# SD_Card.net
KiCad netlist of a schematic drawn in Altium Designer
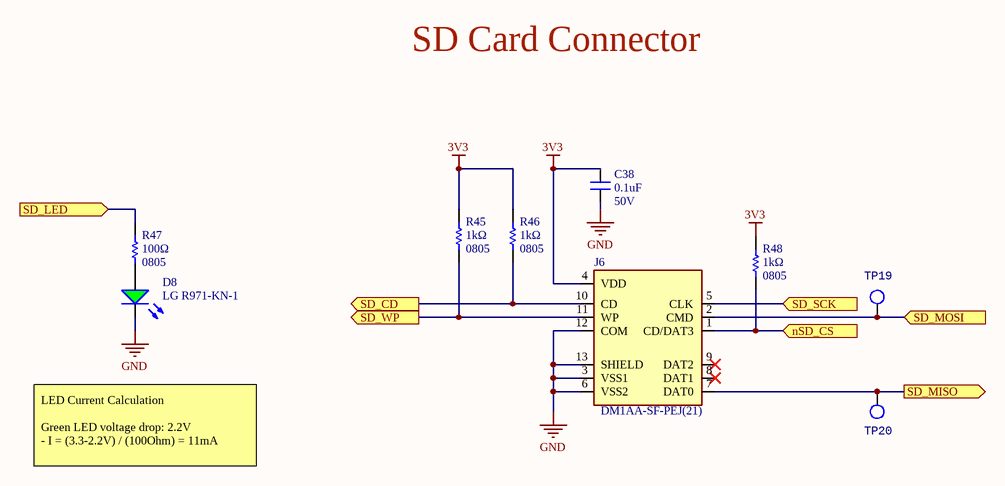
[diagram p0: SD Card.SchDoc]

(export (version "E")
  (design (tool "Eeschema 10.0.6"))
  (components
    (comp (ref "C38")
      (value "0.1uF")
      (footprint "CAPC2012X140N")
      (description "CAP CER 0.1UF 50V X7R 0805")
      (fields
        (field (name "TOLERANCE") "10%")
        (field (name "VOLTAGE RATING") "50V")
        (field (name "Comment") "CAP_0.1uF_50V_0805")
      )
      (libsource (lib "UWRT_Schematic_Library_2020") (part "CAP_0.1uF_50V_0805"))
    )
    (comp (ref "D8")
      (value "DIO_LED_G")
      (footprint "LED_0805_LINE")
      (description "LED GREEN DIFFUSED 0805 SMD")
      (fields (field (name "MANUFACTURER PART NUMBER 1") "LG R971-KN-1"))
      (libsource (lib "UWRT_Schematic_Library_2020") (part "DIO_LED_G"))
    )
    (comp (ref "J6")
      (value "SD_CARD_CON")
      (footprint "HRS_DM1AA-SF-PEJ(21)")
      (description "12 _9 + 3_ Position Card Connector Secure Digital - SD Surface Mount, Right Angle Gold")
      (fields (field (name "MANUFACTURER PART NUMBER 1") "DM1AA-SF-PEJ(21)"))
      (libsource (lib "UWRT_Schematic_Library_2020") (part "SD_CARD_CON"))
    )
    (comp (ref "R45")
      (value "1kΩ")
      (footprint "RESC2012X60N")
      (description "RES SMD 1K OHM 1% 1/8W 0805")
      (fields
        (field (name "CASE CODE (IMPERIAL)") "0805")
        (field (name "TOLERANCE") "1%")
        (field (name "Comment") "RES_1kΩ_0805")
      )
      (libsource (lib "UWRT_Schematic_Library_2020") (part "RES_1kΩ_0805"))
    )
    (comp (ref "R46")
      (value "1kΩ")
      (footprint "RESC2012X60N")
      (description "RES SMD 1K OHM 1% 1/8W 0805")
      (fields
        (field (name "CASE CODE (IMPERIAL)") "0805")
        (field (name "TOLERANCE") "1%")
        (field (name "Comment") "RES_1kΩ_0805")
      )
      (libsource (lib "UWRT_Schematic_Library_2020") (part "RES_1kΩ_0805"))
    )
    (comp (ref "R47")
      (value "100Ω")
      (footprint "RESC2012X60N")
      (description "RES SMD 100 OHM 1% 1/8W 0805")
      (fields (field (name "CASE CODE (IMPERIAL)") "0805") (field (name "Comment") "RES_100Ω_0805"))
      (libsource (lib "UWRT_Schematic_Library_2020") (part "RES_100Ω_0805"))
    )
    (comp (ref "R48")
      (value "1kΩ")
      (footprint "RESC2012X60N")
      (description "RES SMD 1K OHM 1% 1/8W 0805")
      (fields
        (field (name "CASE CODE (IMPERIAL)") "0805")
        (field (name "TOLERANCE") "1%")
        (field (name "Comment") "RES_1kΩ_0805")
      )
      (libsource (lib "UWRT_Schematic_Library_2020") (part "RES_1kΩ_0805"))
    )
    (comp (ref "TP19")
      (value "TESTPOINT_LOOP")
      (footprint "TESTPOINT_LOOP")
      (description "Loop testpoint through-hole pad")
      (libsource (lib "UWRT_Schematic_Library_2020") (part "TESTPOINT_LOOP"))
    )
    (comp (ref "TP20")
      (value "TESTPOINT_LOOP")
      (footprint "TESTPOINT_LOOP")
      (description "Loop testpoint through-hole pad")
      (libsource (lib "UWRT_Schematic_Library_2020") (part "TESTPOINT_LOOP"))
    )
  )
  (nets
    (net (code "1") (name "/SD_CD") (class "Default")
      (node (ref "J6") (pin "10") (pinfunction "CD_10") (pintype "passive"))
      (node (ref "R46") (pin "1") (pinfunction "1_1") (pintype "passive"))
    )
    (net (code "2") (name "/SD_LED") (class "Default")
      (node (ref "R47") (pin "2") (pinfunction "2_2") (pintype "passive"))
    )
    (net (code "3") (name "/SD_MISO") (class "Default")
      (node (ref "J6") (pin "7") (pinfunction "DAT0_7") (pintype "passive"))
      (node (ref "TP20") (pin "1") (pintype "passive"))
    )
    (net (code "4") (name "/SD_MOSI") (class "Default")
      (node (ref "J6") (pin "2") (pinfunction "CMD_2") (pintype "passive"))
      (node (ref "TP19") (pin "1") (pintype "passive"))
    )
    (net (code "5") (name "/SD_SCK") (class "Default")
      (node (ref "J6") (pin "5") (pinfunction "CLK_5") (pintype "passive"))
    )
    (net (code "6") (name "/SD_WP") (class "Default")
      (node (ref "J6") (pin "11") (pinfunction "WP_11") (pintype "passive"))
      (node (ref "R45") (pin "1") (pinfunction "1_1") (pintype "passive"))
    )
    (net (code "7") (name "/nSD_CS") (class "Default")
      (node (ref "J6") (pin "1") (pinfunction "CD/DAT3_1") (pintype "passive"))
      (node (ref "R48") (pin "1") (pinfunction "1_1") (pintype "passive"))
    )
    (net (code "8") (name "3V3") (class "Default")
      (node (ref "C38") (pin "2") (pinfunction "2_2") (pintype "passive"))
      (node (ref "J6") (pin "4") (pinfunction "VDD_4") (pintype "power_in"))
      (node (ref "R45") (pin "2") (pinfunction "2_2") (pintype "passive"))
      (node (ref "R46") (pin "2") (pinfunction "2_2") (pintype "passive"))
      (node (ref "R48") (pin "2") (pinfunction "2_2") (pintype "passive"))
    )
    (net (code "9") (name "GND") (class "Default")
      (node (ref "C38") (pin "1") (pinfunction "1_1") (pintype "passive"))
      (node (ref "D8") (pin "2") (pinfunction "K_2") (pintype "passive"))
      (node (ref "J6") (pin "12") (pinfunction "COM_12") (pintype "passive"))
      (node (ref "J6") (pin "13") (pinfunction "SHIELD_13") (pintype "passive"))
      (node (ref "J6") (pin "3") (pinfunction "VSS1_3") (pintype "power_in"))
      (node (ref "J6") (pin "6") (pinfunction "VSS2_6") (pintype "power_in"))
    )
    (net (code "10") (name "Net-(D8-A)") (class "Default")
      (node (ref "D8") (pin "1") (pinfunction "A_1") (pintype "passive"))
      (node (ref "R47") (pin "1") (pinfunction "1_1") (pintype "passive"))
    )
    (net (code "11") (name "unconnected-(J6-DAT1-Pad8)") (class "Default")
      (node (ref "J6") (pin "8") (pinfunction "DAT1_8") (pintype "passive+no_connect"))
    )
    (net (code "12") (name "unconnected-(J6-DAT2-Pad9)") (class "Default")
      (node (ref "J6") (pin "9") (pinfunction "DAT2_9") (pintype "passive+no_connect"))
    )
  )
)
